# utility_hat.net
KiCad netlist of a schematic drawn in EAGLE
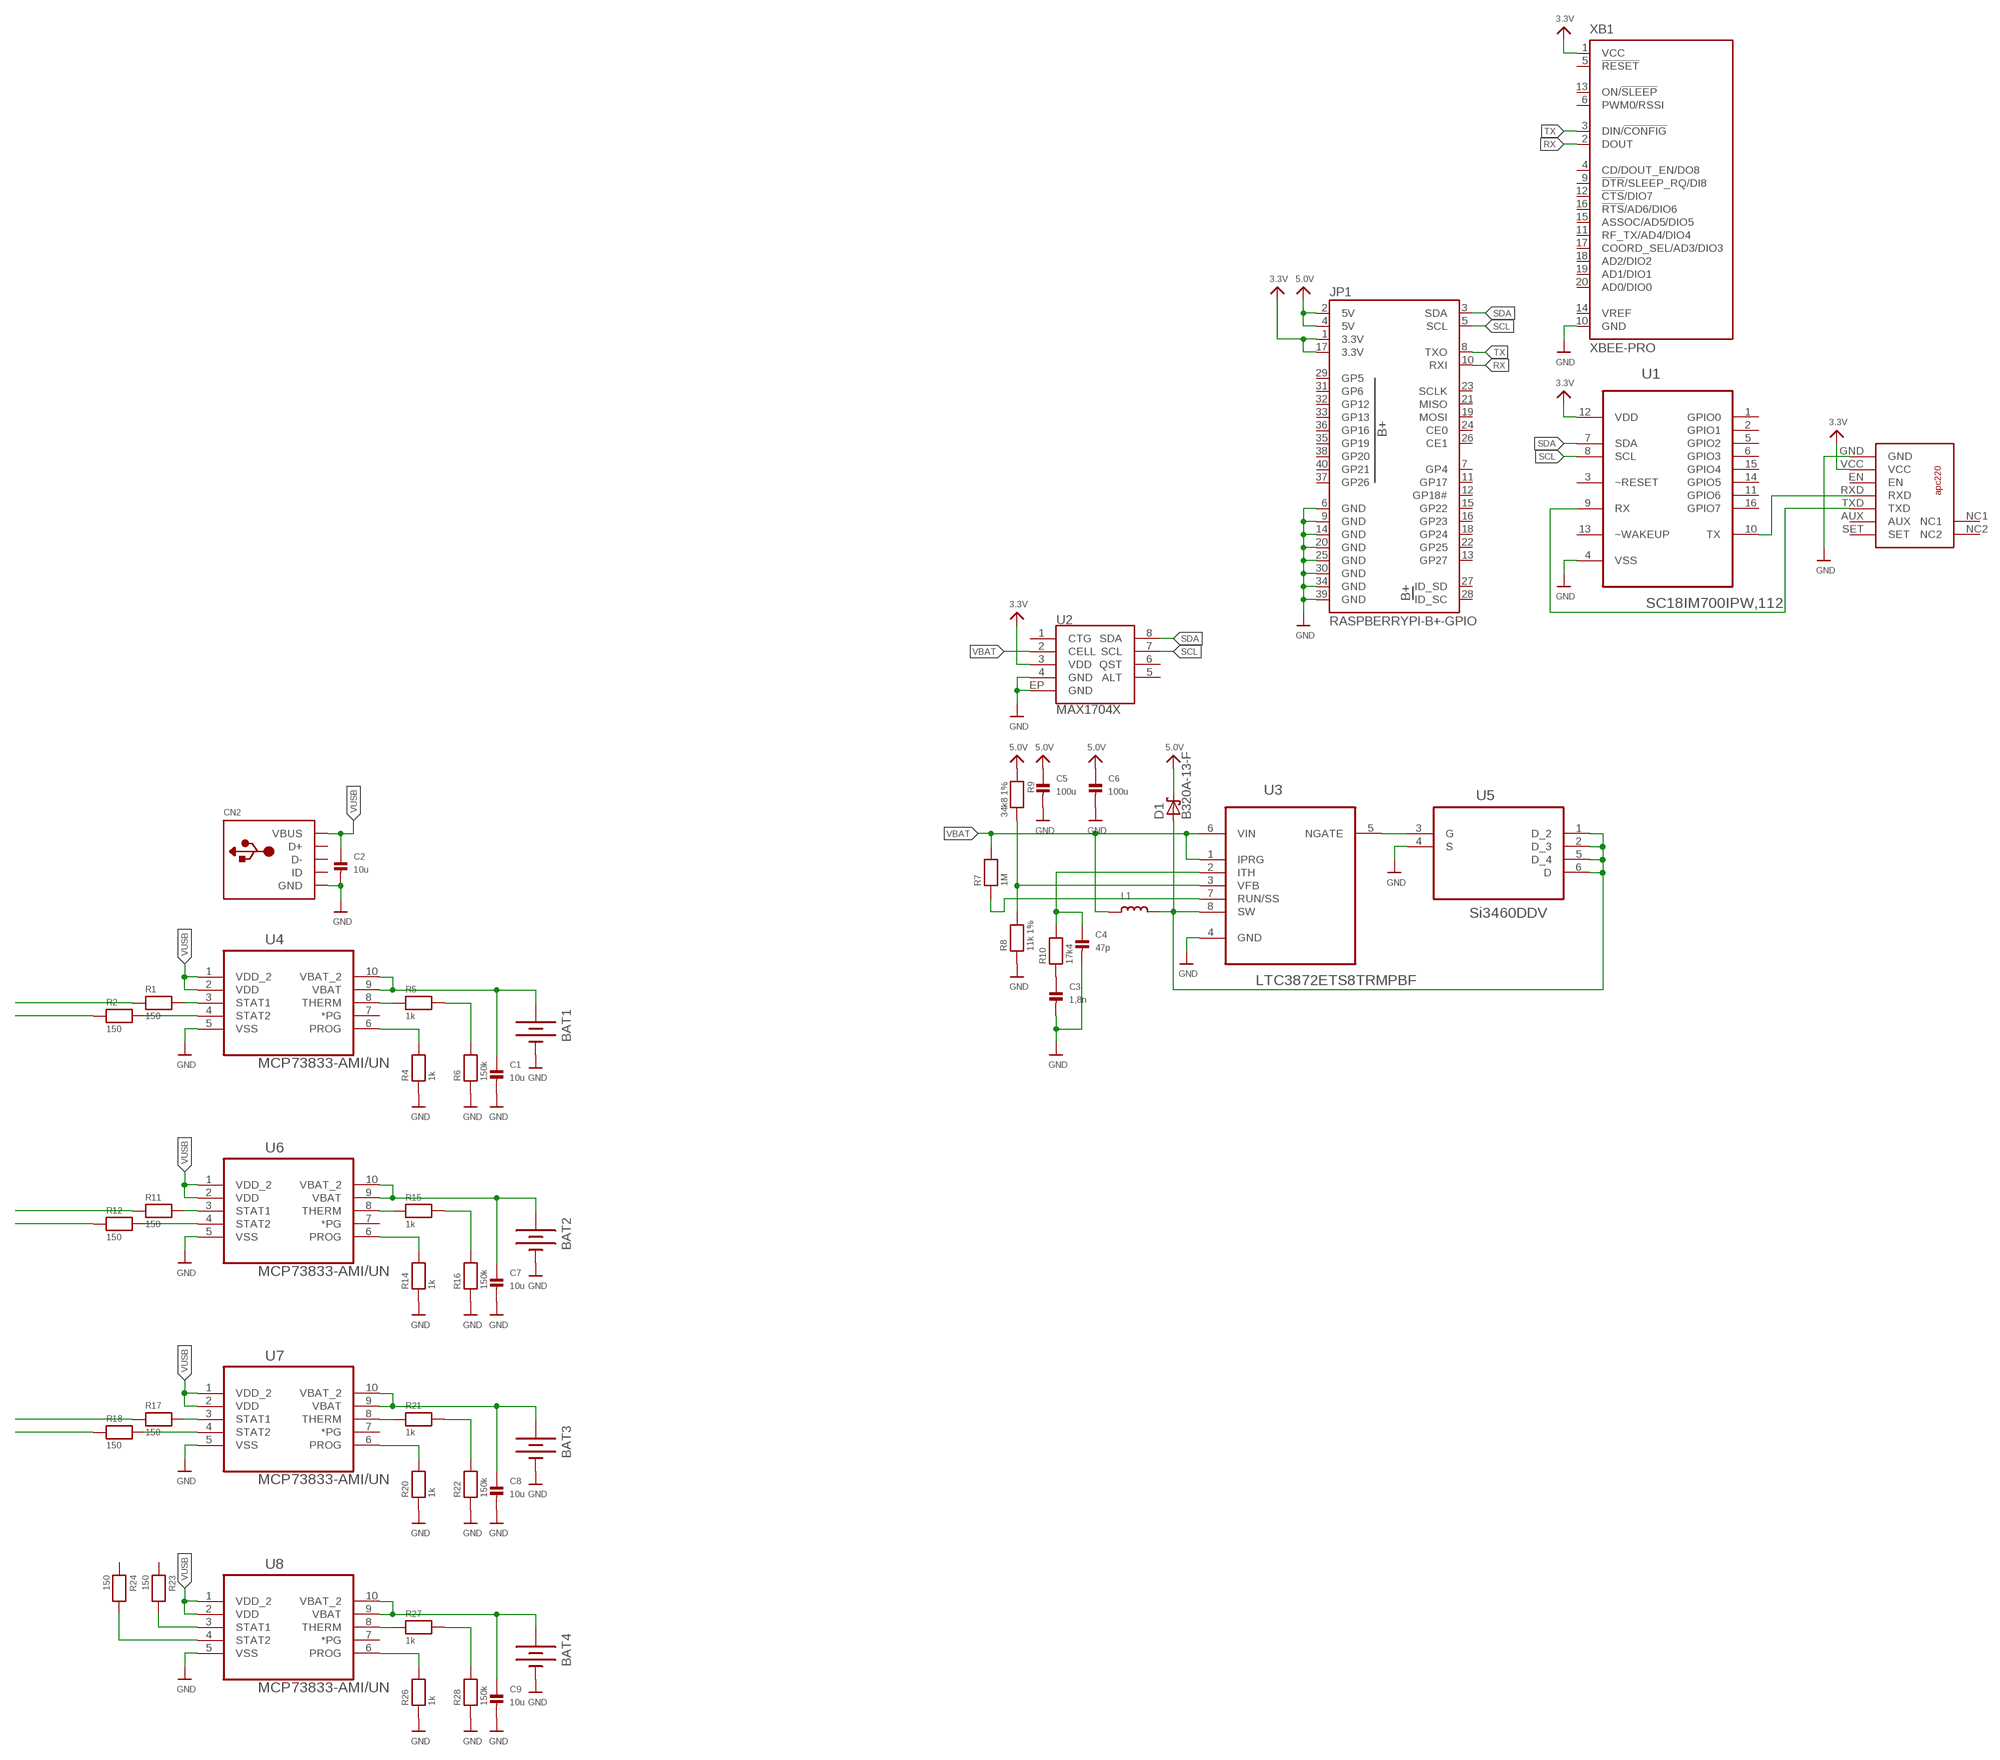
[diagram p0: schematic, sheet 1]

(export (version "E")
  (design (tool "Eeschema 10.0.6"))
  (components
    (comp (ref "BAT1")
      (value "BATTERY18650")
      (footprint "eagle-import:BATTERY_18650-HOLDER")
      (libsource (lib "eagle-import") (part "BATTERY18650"))
    )
    (comp (ref "BAT2")
      (value "BATTERY18650")
      (footprint "eagle-import:BATTERY_18650-HOLDER")
      (libsource (lib "eagle-import") (part "BATTERY18650"))
    )
    (comp (ref "BAT3")
      (value "BATTERY18650")
      (footprint "eagle-import:BATTERY_18650-HOLDER")
      (libsource (lib "eagle-import") (part "BATTERY18650"))
    )
    (comp (ref "BAT4")
      (value "BATTERY18650")
      (footprint "eagle-import:BATTERY_18650-HOLDER")
      (libsource (lib "eagle-import") (part "BATTERY18650"))
    )
    (comp (ref "C1")
      (value "10u")
      (footprint "eagle-import:_0805MP")
      (libsource (lib "eagle-import") (part "CAP_CERAMIC_0805MP"))
    )
    (comp (ref "C2")
      (value "10u")
      (footprint "eagle-import:_0805MP")
      (libsource (lib "eagle-import") (part "CAP_CERAMIC_0805MP"))
    )
    (comp (ref "C3")
      (value "1,8n")
      (footprint "eagle-import:_0603MP")
      (libsource (lib "eagle-import") (part "CAP_CERAMIC_0603MP"))
    )
    (comp (ref "C4")
      (value "47p")
      (footprint "eagle-import:_0603MP")
      (libsource (lib "eagle-import") (part "CAP_CERAMIC_0603MP"))
    )
    (comp (ref "C5")
      (value "100u")
      (footprint "eagle-import:1206")
      (libsource (lib "eagle-import") (part "CAP_CERAMIC1206"))
    )
    (comp (ref "C6")
      (value "100u")
      (footprint "eagle-import:1206")
      (libsource (lib "eagle-import") (part "CAP_CERAMIC1206"))
    )
    (comp (ref "C7")
      (value "10u")
      (footprint "eagle-import:_0805MP")
      (libsource (lib "eagle-import") (part "CAP_CERAMIC_0805MP"))
    )
    (comp (ref "C8")
      (value "10u")
      (footprint "eagle-import:_0805MP")
      (libsource (lib "eagle-import") (part "CAP_CERAMIC_0805MP"))
    )
    (comp (ref "C9")
      (value "10u")
      (footprint "eagle-import:_0805MP")
      (libsource (lib "eagle-import") (part "CAP_CERAMIC_0805MP"))
    )
    (comp (ref "CN2")
      (value "USBMINIB")
      (footprint "eagle-import:USB-MINIB")
      (libsource (lib "eagle-import") (part "USBMINIB"))
    )
    (comp (ref "D1")
      (value "B320A-13-F")
      (footprint "eagle-import:SMC")
      (libsource (lib "eagle-import") (part "MBRS30T32"))
    )
    (comp (ref "JP1")
      (value "RASPBERRYPI-B+-GPIO")
      (footprint "eagle-import:2X20-SHROUDED")
      (libsource (lib "eagle-import") (part "RASPBERRYPI-B+-GPIO"))
    )
    (comp (ref "L1")
      (value "INDUCTOR")
      (footprint "eagle-import:INDUCTOR_1007")
      (libsource (lib "eagle-import") (part "INDUCTOR"))
    )
    (comp (ref "R1")
      (value "150")
      (footprint "eagle-import:_0603MP")
      (libsource (lib "eagle-import") (part "RESISTOR_0603MP"))
    )
    (comp (ref "R2")
      (value "150")
      (footprint "eagle-import:_0603MP")
      (libsource (lib "eagle-import") (part "RESISTOR_0603MP"))
    )
    (comp (ref "R4")
      (value "1k")
      (footprint "eagle-import:_0603MP")
      (libsource (lib "eagle-import") (part "RESISTOR_0603MP"))
    )
    (comp (ref "R5")
      (value "1k")
      (footprint "eagle-import:_0603MP")
      (libsource (lib "eagle-import") (part "RESISTOR_0603MP"))
    )
    (comp (ref "R6")
      (value "150k")
      (footprint "eagle-import:_0603MP")
      (libsource (lib "eagle-import") (part "RESISTOR_0603MP"))
    )
    (comp (ref "R7")
      (value "1M")
      (footprint "eagle-import:_0603MP")
      (libsource (lib "eagle-import") (part "RESISTOR_0603MP"))
    )
    (comp (ref "R8")
      (value "11k 1%")
      (footprint "eagle-import:_0603MP")
      (libsource (lib "eagle-import") (part "RESISTOR_0603MP"))
    )
    (comp (ref "R9")
      (value "34k8 1%")
      (footprint "eagle-import:_0603MP")
      (libsource (lib "eagle-import") (part "RESISTOR_0603MP"))
    )
    (comp (ref "R10")
      (value "17k4")
      (footprint "eagle-import:_0603MP")
      (libsource (lib "eagle-import") (part "RESISTOR_0603MP"))
    )
    (comp (ref "R11")
      (value "150")
      (footprint "eagle-import:_0603MP")
      (libsource (lib "eagle-import") (part "RESISTOR_0603MP"))
    )
    (comp (ref "R12")
      (value "150")
      (footprint "eagle-import:_0603MP")
      (libsource (lib "eagle-import") (part "RESISTOR_0603MP"))
    )
    (comp (ref "R14")
      (value "1k")
      (footprint "eagle-import:_0603MP")
      (libsource (lib "eagle-import") (part "RESISTOR_0603MP"))
    )
    (comp (ref "R15")
      (value "1k")
      (footprint "eagle-import:_0603MP")
      (libsource (lib "eagle-import") (part "RESISTOR_0603MP"))
    )
    (comp (ref "R16")
      (value "150k")
      (footprint "eagle-import:_0603MP")
      (libsource (lib "eagle-import") (part "RESISTOR_0603MP"))
    )
    (comp (ref "R17")
      (value "150")
      (footprint "eagle-import:_0603MP")
      (libsource (lib "eagle-import") (part "RESISTOR_0603MP"))
    )
    (comp (ref "R18")
      (value "150")
      (footprint "eagle-import:_0603MP")
      (libsource (lib "eagle-import") (part "RESISTOR_0603MP"))
    )
    (comp (ref "R20")
      (value "1k")
      (footprint "eagle-import:_0603MP")
      (libsource (lib "eagle-import") (part "RESISTOR_0603MP"))
    )
    (comp (ref "R21")
      (value "1k")
      (footprint "eagle-import:_0603MP")
      (libsource (lib "eagle-import") (part "RESISTOR_0603MP"))
    )
    (comp (ref "R22")
      (value "150k")
      (footprint "eagle-import:_0603MP")
      (libsource (lib "eagle-import") (part "RESISTOR_0603MP"))
    )
    (comp (ref "R23")
      (value "150")
      (footprint "eagle-import:_0603MP")
      (libsource (lib "eagle-import") (part "RESISTOR_0603MP"))
    )
    (comp (ref "R24")
      (value "150")
      (footprint "eagle-import:_0603MP")
      (libsource (lib "eagle-import") (part "RESISTOR_0603MP"))
    )
    (comp (ref "R26")
      (value "1k")
      (footprint "eagle-import:_0603MP")
      (libsource (lib "eagle-import") (part "RESISTOR_0603MP"))
    )
    (comp (ref "R27")
      (value "1k")
      (footprint "eagle-import:_0603MP")
      (libsource (lib "eagle-import") (part "RESISTOR_0603MP"))
    )
    (comp (ref "R28")
      (value "150k")
      (footprint "eagle-import:_0603MP")
      (libsource (lib "eagle-import") (part "RESISTOR_0603MP"))
    )
    (comp (ref "U$10")
      (value "APC220")
      (footprint "eagle-import:APC220")
      (libsource (lib "eagle-import") (part "APC220"))
    )
    (comp (ref "U1")
      (value "SC18IM700IPW,112")
      (footprint "eagle-import:SOP65P640X110-16N")
      (libsource (lib "eagle-import") (part "SC18IM700IPW,112"))
    )
    (comp (ref "U2")
      (value "MAX1704X")
      (footprint "eagle-import:TDFN-8")
      (libsource (lib "eagle-import") (part "MAX1704X"))
    )
    (comp (ref "U3")
      (value "LTC3872ETS8TRMPBF")
      (footprint "eagle-import:SOT65P280X100-8N")
      (fields (field (name "MPN") "LTC3872ETS8#TRMPBF"))
      (libsource (lib "eagle-import") (part "LTC3872ETS8TRMPBF"))
    )
    (comp (ref "U4")
      (value "MCP73833-AMI/UN")
      (footprint "eagle-import:SOP50P490X110-10N")
      (libsource (lib "eagle-import") (part "MCP73833-AMI/UN"))
    )
    (comp (ref "U5")
      (value "Si3460DDV")
      (footprint "eagle-import:SOT95P285X110-6N")
      (fields (field (name "MPN") "SI3457CDV-T1-GE3"))
      (libsource (lib "eagle-import") (part "SI3457CDV-T1-GE3"))
    )
    (comp (ref "U6")
      (value "MCP73833-AMI/UN")
      (footprint "eagle-import:SOP50P490X110-10N")
      (libsource (lib "eagle-import") (part "MCP73833-AMI/UN"))
    )
    (comp (ref "U7")
      (value "MCP73833-AMI/UN")
      (footprint "eagle-import:SOP50P490X110-10N")
      (libsource (lib "eagle-import") (part "MCP73833-AMI/UN"))
    )
    (comp (ref "U8")
      (value "MCP73833-AMI/UN")
      (footprint "eagle-import:SOP50P490X110-10N")
      (libsource (lib "eagle-import") (part "MCP73833-AMI/UN"))
    )
    (comp (ref "XB1")
      (value "XBEE-PRO")
      (footprint "eagle-import:XBEE-PRO")
      (libsource (lib "eagle-import") (part "XBEE-PRO"))
    )
  )
  (nets
    (net (code "1") (name "3.3V") (class "Default")
      (node (ref "JP1") (pin "1") (pinfunction "3.3V_1") (pintype "power_in"))
      (node (ref "JP1") (pin "17") (pinfunction "3.3V_17") (pintype "power_in"))
      (node (ref "U$10") (pin "VCC") (pinfunction "VCC_VCC") (pintype "bidirectional"))
      (node (ref "U1") (pin "12") (pinfunction "VDD_12") (pintype "power_in"))
      (node (ref "U2") (pin "3") (pinfunction "VDD_3") (pintype "bidirectional"))
      (node (ref "XB1") (pin "1") (pinfunction "VCC_1") (pintype "power_in"))
    )
    (net (code "2") (name "5.0V") (class "Default")
      (node (ref "C5") (pin "1") (pinfunction "P$1_1") (pintype "passive"))
      (node (ref "C6") (pin "1") (pinfunction "P$1_1") (pintype "passive"))
      (node (ref "D1") (pin "C") (pinfunction "C_C") (pintype "passive"))
      (node (ref "JP1") (pin "2") (pinfunction "5V_2") (pintype "power_in"))
      (node (ref "JP1") (pin "4") (pinfunction "5V_4") (pintype "power_in"))
      (node (ref "R9") (pin "1") (pinfunction "1_1") (pintype "passive"))
    )
    (net (code "3") (name "GND") (class "Default")
      (node (ref "BAT1") (pin "GND@1") (pinfunction "-_GND@1") (pintype "power_in"))
      (node (ref "BAT2") (pin "GND@1") (pinfunction "-_GND@1") (pintype "power_in"))
      (node (ref "BAT3") (pin "GND@1") (pinfunction "-_GND@1") (pintype "power_in"))
      (node (ref "BAT4") (pin "GND@1") (pinfunction "-_GND@1") (pintype "power_in"))
      (node (ref "C1") (pin "2") (pinfunction "P$2_2") (pintype "passive"))
      (node (ref "C2") (pin "2") (pinfunction "P$2_2") (pintype "passive"))
      (node (ref "C3") (pin "2") (pinfunction "P$2_2") (pintype "passive"))
      (node (ref "C4") (pin "2") (pinfunction "P$2_2") (pintype "passive"))
      (node (ref "C5") (pin "2") (pinfunction "P$2_2") (pintype "passive"))
      (node (ref "C6") (pin "2") (pinfunction "P$2_2") (pintype "passive"))
      (node (ref "C7") (pin "2") (pinfunction "P$2_2") (pintype "passive"))
      (node (ref "C8") (pin "2") (pinfunction "P$2_2") (pintype "passive"))
      (node (ref "C9") (pin "2") (pinfunction "P$2_2") (pintype "passive"))
      (node (ref "CN2") (pin "GND") (pinfunction "GND_GND") (pintype "power_in"))
      (node (ref "JP1") (pin "14") (pinfunction "GND_14") (pintype "power_in"))
      (node (ref "JP1") (pin "20") (pinfunction "GND_20") (pintype "power_in"))
      (node (ref "JP1") (pin "25") (pinfunction "GND_25") (pintype "power_in"))
      (node (ref "JP1") (pin "30") (pinfunction "GND_30") (pintype "power_in"))
      (node (ref "JP1") (pin "34") (pinfunction "GND_34") (pintype "power_in"))
      (node (ref "JP1") (pin "39") (pinfunction "GND_39") (pintype "power_in"))
      (node (ref "JP1") (pin "6") (pinfunction "GND_6") (pintype "power_in"))
      (node (ref "JP1") (pin "9") (pinfunction "GND_9") (pintype "power_in"))
      (node (ref "R14") (pin "1") (pinfunction "1_1") (pintype "passive"))
      (node (ref "R16") (pin "1") (pinfunction "1_1") (pintype "passive"))
      (node (ref "R20") (pin "1") (pinfunction "1_1") (pintype "passive"))
      (node (ref "R22") (pin "1") (pinfunction "1_1") (pintype "passive"))
      (node (ref "R26") (pin "1") (pinfunction "1_1") (pintype "passive"))
      (node (ref "R28") (pin "1") (pinfunction "1_1") (pintype "passive"))
      (node (ref "R4") (pin "1") (pinfunction "1_1") (pintype "passive"))
      (node (ref "R6") (pin "1") (pinfunction "1_1") (pintype "passive"))
      (node (ref "R8") (pin "1") (pinfunction "1_1") (pintype "passive"))
      (node (ref "U$10") (pin "GND") (pinfunction "GND_GND") (pintype "bidirectional"))
      (node (ref "U1") (pin "4") (pinfunction "VSS_4") (pintype "passive"))
      (node (ref "U2") (pin "4") (pinfunction "GND_4") (pintype "bidirectional"))
      (node (ref "U2") (pin "EP") (pinfunction "GND_EP") (pintype "bidirectional"))
      (node (ref "U3") (pin "4") (pinfunction "GND_4") (pintype "passive"))
      (node (ref "U4") (pin "5") (pinfunction "VSS_5") (pintype "passive"))
      (node (ref "U5") (pin "4") (pinfunction "S_4") (pintype "passive"))
      (node (ref "U6") (pin "5") (pinfunction "VSS_5") (pintype "passive"))
      (node (ref "U7") (pin "5") (pinfunction "VSS_5") (pintype "passive"))
      (node (ref "U8") (pin "5") (pinfunction "VSS_5") (pintype "passive"))
      (node (ref "XB1") (pin "10") (pinfunction "GND_10") (pintype "power_in"))
    )
    (net (code "4") (name "Net-(BAT1-+)") (class "Default")
      (node (ref "BAT1") (pin "PWR@1") (pinfunction "+_PWR@1") (pintype "power_in"))
      (node (ref "C1") (pin "1") (pinfunction "P$1_1") (pintype "passive"))
      (node (ref "U4") (pin "10") (pinfunction "VBAT_2_10") (pintype "output"))
      (node (ref "U4") (pin "9") (pinfunction "VBAT_9") (pintype "output"))
    )
    (net (code "5") (name "Net-(BAT2-+)") (class "Default")
      (node (ref "BAT2") (pin "PWR@1") (pinfunction "+_PWR@1") (pintype "power_in"))
      (node (ref "C7") (pin "1") (pinfunction "P$1_1") (pintype "passive"))
      (node (ref "U6") (pin "10") (pinfunction "VBAT_2_10") (pintype "output"))
      (node (ref "U6") (pin "9") (pinfunction "VBAT_9") (pintype "output"))
    )
    (net (code "6") (name "Net-(BAT3-+)") (class "Default")
      (node (ref "BAT3") (pin "PWR@1") (pinfunction "+_PWR@1") (pintype "power_in"))
      (node (ref "C8") (pin "1") (pinfunction "P$1_1") (pintype "passive"))
      (node (ref "U7") (pin "10") (pinfunction "VBAT_2_10") (pintype "output"))
      (node (ref "U7") (pin "9") (pinfunction "VBAT_9") (pintype "output"))
    )
    (net (code "7") (name "Net-(BAT4-+)") (class "Default")
      (node (ref "BAT4") (pin "PWR@1") (pinfunction "+_PWR@1") (pintype "power_in"))
      (node (ref "C9") (pin "1") (pinfunction "P$1_1") (pintype "passive"))
      (node (ref "U8") (pin "10") (pinfunction "VBAT_2_10") (pintype "output"))
      (node (ref "U8") (pin "9") (pinfunction "VBAT_9") (pintype "output"))
    )
    (net (code "8") (name "Net-(C3-P$1)") (class "Default")
      (node (ref "C3") (pin "1") (pinfunction "P$1_1") (pintype "passive"))
      (node (ref "R10") (pin "1") (pinfunction "1_1") (pintype "passive"))
    )
    (net (code "9") (name "Net-(C4-P$1)") (class "Default")
      (node (ref "C4") (pin "1") (pinfunction "P$1_1") (pintype "passive"))
      (node (ref "R10") (pin "2") (pinfunction "2_2") (pintype "passive"))
      (node (ref "U3") (pin "2") (pinfunction "ITH_2") (pintype "input"))
    )
    (net (code "10") (name "Net-(L1-2)") (class "Default")
      (node (ref "D1") (pin "A") (pinfunction "A_A") (pintype "passive"))
      (node (ref "L1") (pin "P$2") (pinfunction "2_P$2") (pintype "passive"))
      (node (ref "U3") (pin "8") (pinfunction "SW_8") (pintype "passive"))
      (node (ref "U5") (pin "1") (pinfunction "D_2_1") (pintype "passive"))
      (node (ref "U5") (pin "2") (pinfunction "D_3_2") (pintype "passive"))
      (node (ref "U5") (pin "5") (pinfunction "D_4_5") (pintype "passive"))
      (node (ref "U5") (pin "6") (pinfunction "D_6") (pintype "passive"))
    )
    (net (code "11") (name "Net-(R5-Pad2)") (class "Default")
      (node (ref "R5") (pin "2") (pinfunction "2_2") (pintype "passive"))
      (node (ref "R6") (pin "2") (pinfunction "2_2") (pintype "passive"))
    )
    (net (code "12") (name "Net-(R15-Pad2)") (class "Default")
      (node (ref "R15") (pin "2") (pinfunction "2_2") (pintype "passive"))
      (node (ref "R16") (pin "2") (pinfunction "2_2") (pintype "passive"))
    )
    (net (code "13") (name "Net-(R21-Pad2)") (class "Default")
      (node (ref "R21") (pin "2") (pinfunction "2_2") (pintype "passive"))
      (node (ref "R22") (pin "2") (pinfunction "2_2") (pintype "passive"))
    )
    (net (code "14") (name "Net-(R27-Pad2)") (class "Default")
      (node (ref "R27") (pin "2") (pinfunction "2_2") (pintype "passive"))
      (node (ref "R28") (pin "2") (pinfunction "2_2") (pintype "passive"))
    )
    (net (code "15") (name "Net-(U1-RX)") (class "Default")
      (node (ref "U$10") (pin "TXD") (pinfunction "TXD_TXD") (pintype "bidirectional"))
      (node (ref "U1") (pin "9") (pinfunction "RX_9") (pintype "input"))
    )
    (net (code "16") (name "Net-(U1-TX)") (class "Default")
      (node (ref "U$10") (pin "RXD") (pinfunction "RXD_RXD") (pintype "bidirectional"))
      (node (ref "U1") (pin "10") (pinfunction "TX_10") (pintype "output"))
    )
    (net (code "17") (name "Net-(U3-NGATE)") (class "Default")
      (node (ref "U3") (pin "5") (pinfunction "NGATE_5") (pintype "output"))
      (node (ref "U5") (pin "3") (pinfunction "G_3") (pintype "passive"))
    )
    (net (code "18") (name "Net-(U3-RUN{slash}SS)") (class "Default")
      (node (ref "R7") (pin "1") (pinfunction "1_1") (pintype "passive"))
      (node (ref "U3") (pin "7") (pinfunction "RUN/SS_7") (pintype "input"))
    )
    (net (code "19") (name "Net-(U3-VFB)") (class "Default")
      (node (ref "R8") (pin "2") (pinfunction "2_2") (pintype "passive"))
      (node (ref "R9") (pin "2") (pinfunction "2_2") (pintype "passive"))
      (node (ref "U3") (pin "3") (pinfunction "VFB_3") (pintype "input"))
    )
    (net (code "20") (name "Net-(U4-PROG)") (class "Default")
      (node (ref "R4") (pin "2") (pinfunction "2_2") (pintype "passive"))
      (node (ref "U4") (pin "6") (pinfunction "PROG_6") (pintype "input"))
    )
    (net (code "21") (name "Net-(U4-STAT1)") (class "Default")
      (node (ref "R1") (pin "2") (pinfunction "2_2") (pintype "passive"))
      (node (ref "U4") (pin "3") (pinfunction "STAT1_3") (pintype "input"))
    )
    (net (code "22") (name "Net-(U4-STAT2)") (class "Default")
      (node (ref "R2") (pin "2") (pinfunction "2_2") (pintype "passive"))
      (node (ref "U4") (pin "4") (pinfunction "STAT2_4") (pintype "input"))
    )
    (net (code "23") (name "Net-(U4-THERM)") (class "Default")
      (node (ref "R5") (pin "1") (pinfunction "1_1") (pintype "passive"))
      (node (ref "U4") (pin "8") (pinfunction "THERM_8") (pintype "input"))
    )
    (net (code "24") (name "Net-(U6-PROG)") (class "Default")
      (node (ref "R14") (pin "2") (pinfunction "2_2") (pintype "passive"))
      (node (ref "U6") (pin "6") (pinfunction "PROG_6") (pintype "input"))
    )
    (net (code "25") (name "Net-(U6-STAT1)") (class "Default")
      (node (ref "R11") (pin "2") (pinfunction "2_2") (pintype "passive"))
      (node (ref "U6") (pin "3") (pinfunction "STAT1_3") (pintype "input"))
    )
    (net (code "26") (name "Net-(U6-STAT2)") (class "Default")
      (node (ref "R12") (pin "2") (pinfunction "2_2") (pintype "passive"))
      (node (ref "U6") (pin "4") (pinfunction "STAT2_4") (pintype "input"))
    )
    (net (code "27") (name "Net-(U6-THERM)") (class "Default")
      (node (ref "R15") (pin "1") (pinfunction "1_1") (pintype "passive"))
      (node (ref "U6") (pin "8") (pinfunction "THERM_8") (pintype "input"))
    )
    (net (code "28") (name "Net-(U7-PROG)") (class "Default")
      (node (ref "R20") (pin "2") (pinfunction "2_2") (pintype "passive"))
      (node (ref "U7") (pin "6") (pinfunction "PROG_6") (pintype "input"))
    )
    (net (code "29") (name "Net-(U7-STAT1)") (class "Default")
      (node (ref "R17") (pin "2") (pinfunction "2_2") (pintype "passive"))
      (node (ref "U7") (pin "3") (pinfunction "STAT1_3") (pintype "input"))
    )
    (net (code "30") (name "Net-(U7-STAT2)") (class "Default")
      (node (ref "R18") (pin "2") (pinfunction "2_2") (pintype "passive"))
      (node (ref "U7") (pin "4") (pinfunction "STAT2_4") (pintype "input"))
    )
    (net (code "31") (name "Net-(U7-THERM)") (class "Default")
      (node (ref "R21") (pin "1") (pinfunction "1_1") (pintype "passive"))
      (node (ref "U7") (pin "8") (pinfunction "THERM_8") (pintype "input"))
    )
    (net (code "32") (name "Net-(U8-PROG)") (class "Default")
      (node (ref "R26") (pin "2") (pinfunction "2_2") (pintype "passive"))
      (node (ref "U8") (pin "6") (pinfunction "PROG_6") (pintype "input"))
    )
    (net (code "33") (name "Net-(U8-STAT1)") (class "Default")
      (node (ref "R23") (pin "2") (pinfunction "2_2") (pintype "passive"))
      (node (ref "U8") (pin "3") (pinfunction "STAT1_3") (pintype "input"))
    )
    (net (code "34") (name "Net-(U8-STAT2)") (class "Default")
      (node (ref "R24") (pin "2") (pinfunction "2_2") (pintype "passive"))
      (node (ref "U8") (pin "4") (pinfunction "STAT2_4") (pintype "input"))
    )
    (net (code "35") (name "Net-(U8-THERM)") (class "Default")
      (node (ref "R27") (pin "1") (pinfunction "1_1") (pintype "passive"))
      (node (ref "U8") (pin "8") (pinfunction "THERM_8") (pintype "input"))
    )
    (net (code "36") (name "RX") (class "Default")
      (node (ref "JP1") (pin "10") (pinfunction "RXI_10") (pintype "input"))
      (node (ref "XB1") (pin "2") (pinfunction "DOUT_2") (pintype "output"))
    )
    (net (code "37") (name "SCL") (class "Default")
      (node (ref "JP1") (pin "5") (pinfunction "SCL_5") (pintype "bidirectional"))
      (node (ref "U1") (pin "8") (pinfunction "SCL_8") (pintype "input"))
      (node (ref "U2") (pin "7") (pinfunction "SCL_7") (pintype "bidirectional"))
    )
    (net (code "38") (name "SDA") (class "Default")
      (node (ref "JP1") (pin "3") (pinfunction "SDA_3") (pintype "bidirectional"))
      (node (ref "U1") (pin "7") (pinfunction "SDA_7") (pintype "bidirectional"))
      (node (ref "U2") (pin "8") (pinfunction "SDA_8") (pintype "bidirectional"))
    )
    (net (code "39") (name "TX") (class "Default")
      (node (ref "JP1") (pin "8") (pinfunction "TXO_8") (pintype "output"))
      (node (ref "XB1") (pin "3") (pinfunction "DIN/~{CONFIG}_3") (pintype "input"))
    )
    (net (code "40") (name "VBAT") (class "Default")
      (node (ref "L1") (pin "P$1") (pinfunction "1_P$1") (pintype "passive"))
      (node (ref "R7") (pin "2") (pinfunction "2_2") (pintype "passive"))
      (node (ref "U2") (pin "2") (pinfunction "CELL_2") (pintype "bidirectional"))
      (node (ref "U3") (pin "1") (pinfunction "IPRG_1") (pintype "input"))
      (node (ref "U3") (pin "6") (pinfunction "VIN_6") (pintype "power_in"))
    )
    (net (code "41") (name "VUSB") (class "Default")
      (node (ref "C2") (pin "1") (pinfunction "P$1_1") (pintype "passive"))
      (node (ref "CN2") (pin "VBUS") (pinfunction "VBUS_VBUS") (pintype "power_in"))
      (node (ref "U4") (pin "1") (pinfunction "VDD_2_1") (pintype "power_in"))
      (node (ref "U4") (pin "2") (pinfunction "VDD_2") (pintype "power_in"))
      (node (ref "U6") (pin "1") (pinfunction "VDD_2_1") (pintype "power_in"))
      (node (ref "U6") (pin "2") (pinfunction "VDD_2") (pintype "power_in"))
      (node (ref "U7") (pin "1") (pinfunction "VDD_2_1") (pintype "power_in"))
      (node (ref "U7") (pin "2") (pinfunction "VDD_2") (pintype "power_in"))
      (node (ref "U8") (pin "1") (pinfunction "VDD_2_1") (pintype "power_in"))
      (node (ref "U8") (pin "2") (pinfunction "VDD_2") (pintype "power_in"))
    )
    (net (code "42") (name "unconnected-(CN2-PadD+)") (class "Default")
      (node (ref "CN2") (pin "D+") (pinfunction "D+_D+") (pintype "bidirectional"))
    )
    (net (code "43") (name "unconnected-(CN2-PadD-)") (class "Default")
      (node (ref "CN2") (pin "D-") (pinfunction "D-_D-") (pintype "bidirectional"))
    )
    (net (code "44") (name "unconnected-(CN2-PadID)") (class "Default")
      (node (ref "CN2") (pin "ID") (pinfunction "ID_ID") (pintype "bidirectional"))
    )
    (net (code "45") (name "unconnected-(JP1-CE0-Pad24)") (class "Default")
      (node (ref "JP1") (pin "24") (pinfunction "CE0_24") (pintype "output"))
    )
    (net (code "46") (name "unconnected-(JP1-CE1-Pad26)") (class "Default")
      (node (ref "JP1") (pin "26") (pinfunction "CE1_26") (pintype "output"))
    )
    (net (code "47") (name "unconnected-(JP1-GP4-Pad7)") (class "Default")
      (node (ref "JP1") (pin "7") (pinfunction "GP4_7") (pintype "bidirectional"))
    )
    (net (code "48") (name "unconnected-(JP1-GP5-Pad29)") (class "Default")
      (node (ref "JP1") (pin "29") (pinfunction "GP5_29") (pintype "bidirectional"))
    )
    (net (code "49") (name "unconnected-(JP1-GP6-Pad31)") (class "Default")
      (node (ref "JP1") (pin "31") (pinfunction "GP6_31") (pintype "bidirectional"))
    )
    (net (code "50") (name "unconnected-(JP1-GP12-Pad32)") (class "Default")
      (node (ref "JP1") (pin "32") (pinfunction "GP12_32") (pintype "bidirectional"))
    )
    (net (code "51") (name "unconnected-(JP1-GP13-Pad33)") (class "Default")
      (node (ref "JP1") (pin "33") (pinfunction "GP13_33") (pintype "bidirectional"))
    )
    (net (code "52") (name "unconnected-(JP1-GP16-Pad36)") (class "Default")
      (node (ref "JP1") (pin "36") (pinfunction "GP16_36") (pintype "bidirectional"))
    )
    (net (code "53") (name "unconnected-(JP1-GP17-Pad11)") (class "Default")
      (node (ref "JP1") (pin "11") (pinfunction "GP17_11") (pintype "bidirectional"))
    )
    (net (code "54") (name "unconnected-(JP1-GP18#-Pad12)") (class "Default")
      (node (ref "JP1") (pin "12") (pinfunction "GP18#_12") (pintype "bidirectional"))
    )
    (net (code "55") (name "unconnected-(JP1-GP19-Pad35)") (class "Default")
      (node (ref "JP1") (pin "35") (pinfunction "GP19_35") (pintype "bidirectional"))
    )
    (net (code "56") (name "unconnected-(JP1-GP20-Pad38)") (class "Default")
      (node (ref "JP1") (pin "38") (pinfunction "GP20_38") (pintype "bidirectional"))
    )
    (net (code "57") (name "unconnected-(JP1-GP21-Pad40)") (class "Default")
      (node (ref "JP1") (pin "40") (pinfunction "GP21_40") (pintype "bidirectional"))
    )
    (net (code "58") (name "unconnected-(JP1-GP22-Pad15)") (class "Default")
      (node (ref "JP1") (pin "15") (pinfunction "GP22_15") (pintype "bidirectional"))
    )
    (net (code "59") (name "unconnected-(JP1-GP23-Pad16)") (class "Default")
      (node (ref "JP1") (pin "16") (pinfunction "GP23_16") (pintype "bidirectional"))
    )
    (net (code "60") (name "unconnected-(JP1-GP24-Pad18)") (class "Default")
      (node (ref "JP1") (pin "18") (pinfunction "GP24_18") (pintype "bidirectional"))
    )
    (net (code "61") (name "unconnected-(JP1-GP25-Pad22)") (class "Default")
      (node (ref "JP1") (pin "22") (pinfunction "GP25_22") (pintype "bidirectional"))
    )
    (net (code "62") (name "unconnected-(JP1-GP26-Pad37)") (class "Default")
      (node (ref "JP1") (pin "37") (pinfunction "GP26_37") (pintype "bidirectional"))
    )
    (net (code "63") (name "unconnected-(JP1-GP27-Pad13)") (class "Default")
      (node (ref "JP1") (pin "13") (pinfunction "GP27_13") (pintype "bidirectional"))
    )
    (net (code "64") (name "unconnected-(JP1-ID_SC-Pad28)") (class "Default")
      (node (ref "JP1") (pin "28") (pinfunction "ID_SC_28") (pintype "bidirectional"))
    )
    (net (code "65") (name "unconnected-(JP1-ID_SD-Pad27)") (class "Default")
      (node (ref "JP1") (pin "27") (pinfunction "ID_SD_27") (pintype "bidirectional"))
    )
    (net (code "66") (name "unconnected-(JP1-MISO-Pad21)") (class "Default")
      (node (ref "JP1") (pin "21") (pinfunction "MISO_21") (pintype "input"))
    )
    (net (code "67") (name "unconnected-(JP1-MOSI-Pad19)") (class "Default")
      (node (ref "JP1") (pin "19") (pinfunction "MOSI_19") (pintype "output"))
    )
    (net (code "68") (name "unconnected-(JP1-SCLK-Pad23)") (class "Default")
      (node (ref "JP1") (pin "23") (pinfunction "SCLK_23") (pintype "output"))
    )
    (net (code "69") (name "unconnected-(R1-Pad1)") (class "Default")
      (node (ref "R1") (pin "1") (pinfunction "1_1") (pintype "passive"))
    )
    (net (code "70") (name "unconnected-(R2-Pad1)") (class "Default")
      (node (ref "R2") (pin "1") (pinfunction "1_1") (pintype "passive"))
    )
    (net (code "71") (name "unconnected-(R11-Pad1)") (class "Default")
      (node (ref "R11") (pin "1") (pinfunction "1_1") (pintype "passive"))
    )
    (net (code "72") (name "unconnected-(R12-Pad1)") (class "Default")
      (node (ref "R12") (pin "1") (pinfunction "1_1") (pintype "passive"))
    )
    (net (code "73") (name "unconnected-(R17-Pad1)") (class "Default")
      (node (ref "R17") (pin "1") (pinfunction "1_1") (pintype "passive"))
    )
    (net (code "74") (name "unconnected-(R18-Pad1)") (class "Default")
      (node (ref "R18") (pin "1") (pinfunction "1_1") (pintype "passive"))
    )
    (net (code "75") (name "unconnected-(R23-Pad1)") (class "Default")
      (node (ref "R23") (pin "1") (pinfunction "1_1") (pintype "passive"))
    )
    (net (code "76") (name "unconnected-(R24-Pad1)") (class "Default")
      (node (ref "R24") (pin "1") (pinfunction "1_1") (pintype "passive"))
    )
    (net (code "77") (name "unconnected-(U$10-PadAUX)") (class "Default")
      (node (ref "U$10") (pin "AUX") (pinfunction "AUX_AUX") (pintype "bidirectional"))
    )
    (net (code "78") (name "unconnected-(U$10-PadEN)") (class "Default")
      (node (ref "U$10") (pin "EN") (pinfunction "EN_EN") (pintype "bidirectional"))
    )
    (net (code "79") (name "unconnected-(U$10-PadNC1)") (class "Default")
      (node (ref "U$10") (pin "NC1") (pinfunction "NC1_NC1") (pintype "bidirectional"))
    )
    (net (code "80") (name "unconnected-(U$10-PadNC2)") (class "Default")
      (node (ref "U$10") (pin "NC2") (pinfunction "NC2_NC2") (pintype "bidirectional"))
    )
    (net (code "81") (name "unconnected-(U$10-PadSET)") (class "Default")
      (node (ref "U$10") (pin "SET") (pinfunction "SET_SET") (pintype "bidirectional"))
    )
    (net (code "82") (name "unconnected-(U1-GPIO0-Pad1)") (class "Default")
      (node (ref "U1") (pin "1") (pinfunction "GPIO0_1") (pintype "bidirectional"))
    )
    (net (code "83") (name "unconnected-(U1-GPIO1-Pad2)") (class "Default")
      (node (ref "U1") (pin "2") (pinfunction "GPIO1_2") (pintype "bidirectional"))
    )
    (net (code "84") (name "unconnected-(U1-GPIO2-Pad5)") (class "Default")
      (node (ref "U1") (pin "5") (pinfunction "GPIO2_5") (pintype "bidirectional"))
    )
    (net (code "85") (name "unconnected-(U1-GPIO3-Pad6)") (class "Default")
      (node (ref "U1") (pin "6") (pinfunction "GPIO3_6") (pintype "bidirectional"))
    )
    (net (code "86") (name "unconnected-(U1-GPIO4-Pad15)") (class "Default")
      (node (ref "U1") (pin "15") (pinfunction "GPIO4_15") (pintype "bidirectional"))
    )
    (net (code "87") (name "unconnected-(U1-GPIO5-Pad14)") (class "Default")
      (node (ref "U1") (pin "14") (pinfunction "GPIO5_14") (pintype "bidirectional"))
    )
    (net (code "88") (name "unconnected-(U1-GPIO6-Pad11)") (class "Default")
      (node (ref "U1") (pin "11") (pinfunction "GPIO6_11") (pintype "bidirectional"))
    )
    (net (code "89") (name "unconnected-(U1-GPIO7-Pad16)") (class "Default")
      (node (ref "U1") (pin "16") (pinfunction "GPIO7_16") (pintype "bidirectional"))
    )
    (net (code "90") (name "unconnected-(U1-~{RESET}-Pad3)") (class "Default")
      (node (ref "U1") (pin "3") (pinfunction "~{RESET}_3") (pintype "input"))
    )
    (net (code "91") (name "unconnected-(U1-~{WAKEUP}-Pad13)") (class "Default")
      (node (ref "U1") (pin "13") (pinfunction "~{WAKEUP}_13") (pintype "input"))
    )
    (net (code "92") (name "unconnected-(U2-ALT-Pad5)") (class "Default")
      (node (ref "U2") (pin "5") (pinfunction "ALT_5") (pintype "bidirectional"))
    )
    (net (code "93") (name "unconnected-(U2-CTG-Pad1)") (class "Default")
      (node (ref "U2") (pin "1") (pinfunction "CTG_1") (pintype "bidirectional"))
    )
    (net (code "94") (name "unconnected-(U2-QST-Pad6)") (class "Default")
      (node (ref "U2") (pin "6") (pinfunction "QST_6") (pintype "bidirectional"))
    )
    (net (code "95") (name "unconnected-(U4-*PG-Pad7)") (class "Default")
      (node (ref "U4") (pin "7") (pinfunction "*PG_7") (pintype "input"))
    )
    (net (code "96") (name "unconnected-(U6-*PG-Pad7)") (class "Default")
      (node (ref "U6") (pin "7") (pinfunction "*PG_7") (pintype "input"))
    )
    (net (code "97") (name "unconnected-(U7-*PG-Pad7)") (class "Default")
      (node (ref "U7") (pin "7") (pinfunction "*PG_7") (pintype "input"))
    )
    (net (code "98") (name "unconnected-(U8-*PG-Pad7)") (class "Default")
      (node (ref "U8") (pin "7") (pinfunction "*PG_7") (pintype "input"))
    )
    (net (code "99") (name "unconnected-(XB1-AD0{slash}DIO0-Pad20)") (class "Default")
      (node (ref "XB1") (pin "20") (pinfunction "AD0/DIO0_20") (pintype "bidirectional"))
    )
    (net (code "100") (name "unconnected-(XB1-AD1{slash}DIO1-Pad19)") (class "Default")
      (node (ref "XB1") (pin "19") (pinfunction "AD1/DIO1_19") (pintype "bidirectional"))
    )
    (net (code "101") (name "unconnected-(XB1-AD2{slash}DIO2-Pad18)") (class "Default")
      (node (ref "XB1") (pin "18") (pinfunction "AD2/DIO2_18") (pintype "bidirectional"))
    )
    (net (code "102") (name "unconnected-(XB1-ASSOC{slash}AD5{slash}DIO5-Pad15)") (class "Default")
      (node (ref "XB1") (pin "15") (pinfunction "ASSOC/AD5/DIO5_15") (pintype "bidirectional"))
    )
    (net (code "103") (name "unconnected-(XB1-CD{slash}DOUT_EN{slash}DO8-Pad4)") (class "Default")
      (node (ref "XB1") (pin "4") (pinfunction "CD/DOUT_EN/DO8_4") (pintype "output"))
    )
    (net (code "104") (name "unconnected-(XB1-COORD_SEL{slash}AD3{slash}DIO3-Pad17)") (class "Default")
      (node (ref "XB1") (pin "17") (pinfunction "COORD_SEL/AD3/DIO3_17") (pintype "bidirectional"))
    )
    (net (code "105") (name "unconnected-(XB1-ON{slash}~{SLEEP}-Pad13)") (class "Default")
      (node (ref "XB1") (pin "13") (pinfunction "ON/~{SLEEP}_13") (pintype "output"))
    )
    (net (code "106") (name "unconnected-(XB1-PWM0{slash}RSSI-Pad6)") (class "Default")
      (node (ref "XB1") (pin "6") (pinfunction "PWM0/RSSI_6") (pintype "output"))
    )
    (net (code "107") (name "unconnected-(XB1-RF_TX{slash}AD4{slash}DIO4-Pad11)") (class "Default")
      (node (ref "XB1") (pin "11") (pinfunction "RF_TX/AD4/DIO4_11") (pintype "bidirectional"))
    )
    (net (code "108") (name "unconnected-(XB1-VREF-Pad14)") (class "Default")
      (node (ref "XB1") (pin "14") (pinfunction "VREF_14") (pintype "input"))
    )
    (net (code "109") (name "unconnected-(XB1-~{CTS}{slash}DIO7-Pad12)") (class "Default")
      (node (ref "XB1") (pin "12") (pinfunction "~{CTS}/DIO7_12") (pintype "bidirectional"))
    )
    (net (code "110") (name "unconnected-(XB1-~{DTR}{slash}SLEEP_RQ{slash}DI8-Pad9)") (class "Default")
      (node (ref "XB1") (pin "9") (pinfunction "~{DTR}/SLEEP_RQ/DI8_9") (pintype "bidirectional"))
    )
    (net (code "111") (name "unconnected-(XB1-~{RESET}-Pad5)") (class "Default")
      (node (ref "XB1") (pin "5") (pinfunction "~{RESET}_5") (pintype "input"))
    )
    (net (code "112") (name "unconnected-(XB1-~{RTS}{slash}AD6{slash}DIO6-Pad16)") (class "Default")
      (node (ref "XB1") (pin "16") (pinfunction "~{RTS}/AD6/DIO6_16") (pintype "bidirectional"))
    )
  )
)
